# HS_MASTER_SHIELD_MAX485_V1.net
KiCad netlist of a schematic drawn in EAGLE
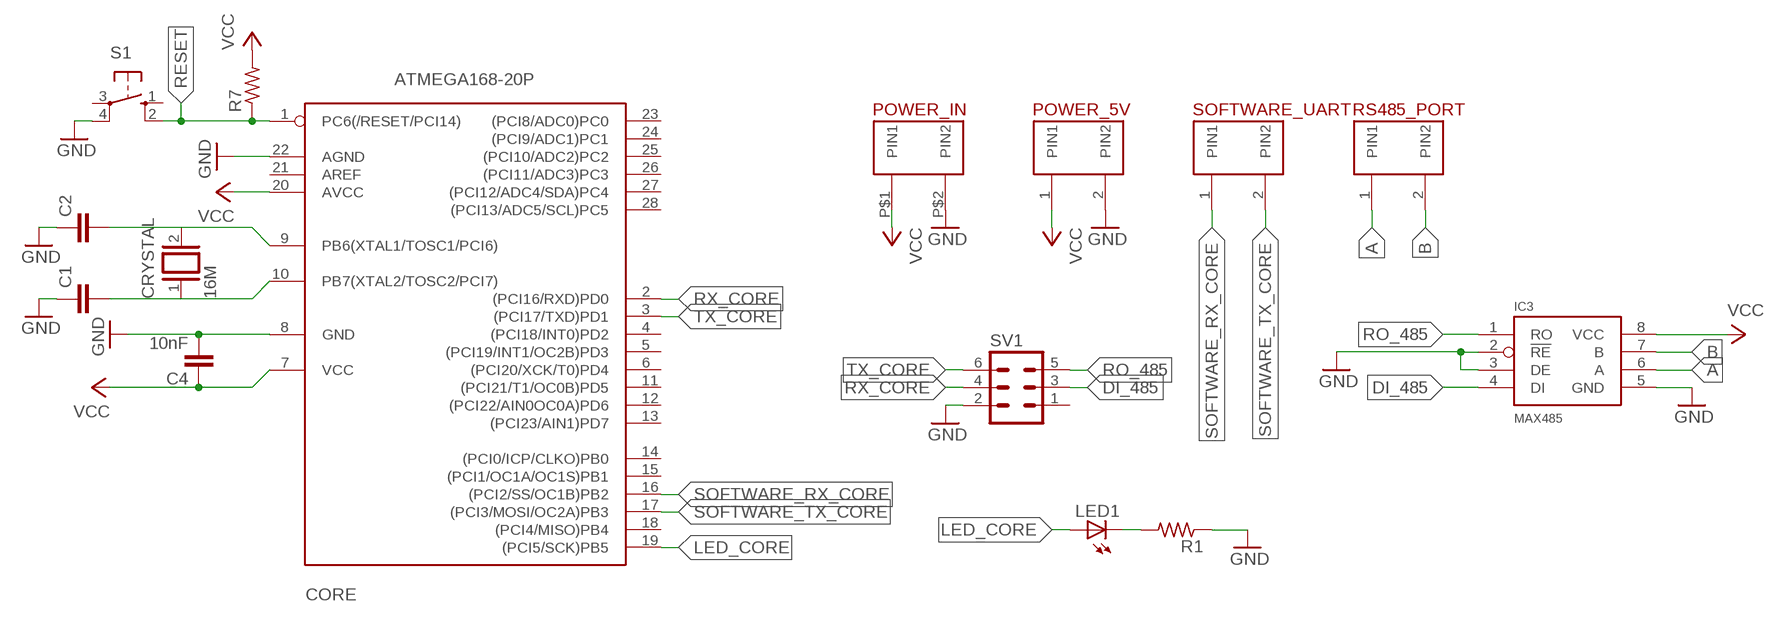
[diagram p0: schematic, sheet 1]

(export (version "E")
  (design (tool "Eeschema 10.0.6"))
  (components
    (comp (ref "C1")
      (value "C-EU025-024X044")
      (footprint "eagle-import:C025-024X044")
      (libsource (lib "eagle-import") (part "C-EU025-024X044"))
    )
    (comp (ref "C2")
      (value "C-EU025-024X044")
      (footprint "eagle-import:C025-024X044")
      (libsource (lib "eagle-import") (part "C-EU025-024X044"))
    )
    (comp (ref "C4")
      (value "10nF")
      (footprint "eagle-import:C5B2.5")
      (libsource (lib "eagle-import") (part "C5/2.5"))
    )
    (comp (ref "CORE")
      (value "ATMEGA168-20P")
      (footprint "eagle-import:DIL28-3")
      (libsource (lib "eagle-import") (part "ATMEGA168P-20"))
    )
    (comp (ref "CRYSTAL")
      (value "16M")
      (footprint "eagle-import:QS")
      (libsource (lib "eagle-import") (part "XTAL/S"))
    )
    (comp (ref "IC3")
      (value "MAX485")
      (footprint "eagle-import:DIP8")
      (libsource (lib "eagle-import") (part "MAX485"))
    )
    (comp (ref "LED1")
      (value "LED3MM")
      (footprint "eagle-import:LED3MM")
      (libsource (lib "eagle-import") (part "LED3MM"))
    )
    (comp (ref "POWER_5V")
      (value "7325")
      (footprint "eagle-import:2.54MM")
      (libsource (lib "eagle-import") (part "7325"))
    )
    (comp (ref "POWER_IN")
      (value "4396")
      (footprint "eagle-import:4MM")
      (libsource (lib "eagle-import") (part "4396"))
    )
    (comp (ref "R1")
      (value "R-US_0207/10")
      (footprint "eagle-import:0207_10")
      (libsource (lib "eagle-import") (part "R-US_0207/10"))
    )
    (comp (ref "R7")
      (value "R-US_0207/10")
      (footprint "eagle-import:0207_10")
      (libsource (lib "eagle-import") (part "R-US_0207/10"))
    )
    (comp (ref "RS485_PORT")
      (value "7325")
      (footprint "eagle-import:2.54MM")
      (libsource (lib "eagle-import") (part "7325"))
    )
    (comp (ref "S1")
      (value "10-XX")
      (footprint "eagle-import:B3F-10XX")
      (fields (field (name "MPN") "B3F-1000"))
      (libsource (lib "eagle-import") (part "10-XX"))
    )
    (comp (ref "SOFTWARE_UART")
      (value "7325")
      (footprint "eagle-import:2.54MM")
      (libsource (lib "eagle-import") (part "7325"))
    )
    (comp (ref "SV1")
      (value "MA03-2")
      (footprint "eagle-import:MA03-2")
      (libsource (lib "eagle-import") (part "MA03-2"))
    )
  )
  (nets
    (net (code "1") (name "A") (class "Default")
      (node (ref "IC3") (pin "6") (pinfunction "A_6") (pintype "bidirectional"))
      (node (ref "RS485_PORT") (pin "1") (pinfunction "PIN1_1") (pintype "bidirectional"))
    )
    (net (code "2") (name "B") (class "Default")
      (node (ref "IC3") (pin "7") (pinfunction "B_7") (pintype "bidirectional"))
      (node (ref "RS485_PORT") (pin "2") (pinfunction "PIN2_2") (pintype "bidirectional"))
    )
    (net (code "3") (name "DI_485") (class "Default")
      (node (ref "IC3") (pin "4") (pinfunction "DI_4") (pintype "bidirectional"))
      (node (ref "SV1") (pin "3") (pinfunction "3_3") (pintype "passive"))
    )
    (net (code "4") (name "GND") (class "Default")
      (node (ref "C1") (pin "1") (pinfunction "1_1") (pintype "passive"))
      (node (ref "C2") (pin "1") (pinfunction "1_1") (pintype "passive"))
      (node (ref "C4") (pin "2") (pinfunction "2_2") (pintype "passive"))
      (node (ref "CORE") (pin "22") (pinfunction "AGND_22") (pintype "bidirectional"))
      (node (ref "CORE") (pin "8") (pinfunction "GND_8") (pintype "bidirectional"))
      (node (ref "IC3") (pin "2") (pinfunction "~{RE}_2") (pintype "bidirectional"))
      (node (ref "IC3") (pin "3") (pinfunction "DE_3") (pintype "bidirectional"))
      (node (ref "IC3") (pin "5") (pinfunction "GND_5") (pintype "bidirectional"))
      (node (ref "POWER_5V") (pin "2") (pinfunction "PIN2_2") (pintype "bidirectional"))
      (node (ref "POWER_IN") (pin "P$2") (pinfunction "PIN2_P$2") (pintype "bidirectional"))
      (node (ref "R1") (pin "1") (pinfunction "1_1") (pintype "passive"))
      (node (ref "S1") (pin "4") (pinfunction "P1_4") (pintype "passive"))
      (node (ref "SV1") (pin "2") (pinfunction "2_2") (pintype "passive"))
    )
    (net (code "5") (name "LED_CORE") (class "Default")
      (node (ref "CORE") (pin "19") (pinfunction "(PCI5/SCK)PB5_19") (pintype "bidirectional"))
      (node (ref "LED1") (pin "A") (pinfunction "A_A") (pintype "passive"))
    )
    (net (code "6") (name "Net-(CORE-PB6(XTAL1{slash}TOSC1{slash}PCI6))") (class "Default")
      (node (ref "C2") (pin "2") (pinfunction "2_2") (pintype "passive"))
      (node (ref "CORE") (pin "9") (pinfunction "PB6(XTAL1/TOSC1/PCI6)_9") (pintype "bidirectional"))
      (node (ref "CRYSTAL") (pin "2") (pinfunction "2_2") (pintype "passive"))
    )
    (net (code "7") (name "Net-(CORE-PB7(XTAL2{slash}TOSC2{slash}PCI7))") (class "Default")
      (node (ref "C1") (pin "2") (pinfunction "2_2") (pintype "passive"))
      (node (ref "CORE") (pin "10") (pinfunction "PB7(XTAL2/TOSC2/PCI7)_10") (pintype "bidirectional"))
      (node (ref "CRYSTAL") (pin "1") (pinfunction "1_1") (pintype "passive"))
    )
    (net (code "8") (name "Net-(LED1-C)") (class "Default")
      (node (ref "LED1") (pin "K") (pinfunction "C_K") (pintype "passive"))
      (node (ref "R1") (pin "2") (pinfunction "2_2") (pintype "passive"))
    )
    (net (code "9") (name "RESET") (class "Default")
      (node (ref "CORE") (pin "1") (pinfunction "PC6(/RESET/PCI14)_1") (pintype "bidirectional"))
      (node (ref "R7") (pin "1") (pinfunction "1_1") (pintype "passive"))
      (node (ref "S1") (pin "2") (pinfunction "S1_2") (pintype "passive"))
    )
    (net (code "10") (name "RO_485") (class "Default")
      (node (ref "IC3") (pin "1") (pinfunction "RO_1") (pintype "bidirectional"))
      (node (ref "SV1") (pin "5") (pinfunction "5_5") (pintype "passive"))
    )
    (net (code "11") (name "RX_CORE") (class "Default")
      (node (ref "CORE") (pin "2") (pinfunction "(PCI16/RXD)PD0_2") (pintype "bidirectional"))
      (node (ref "SV1") (pin "4") (pinfunction "4_4") (pintype "passive"))
    )
    (net (code "12") (name "SOFTWARE_RX_CORE") (class "Default")
      (node (ref "CORE") (pin "16") (pinfunction "(PCI2/SS/OC1B)PB2_16") (pintype "bidirectional"))
      (node (ref "SOFTWARE_UART") (pin "1") (pinfunction "PIN1_1") (pintype "bidirectional"))
    )
    (net (code "13") (name "SOFTWARE_TX_CORE") (class "Default")
      (node (ref "CORE") (pin "17") (pinfunction "(PCI3/MOSI/OC2A)PB3_17") (pintype "bidirectional"))
      (node (ref "SOFTWARE_UART") (pin "2") (pinfunction "PIN2_2") (pintype "bidirectional"))
    )
    (net (code "14") (name "TX_CORE") (class "Default")
      (node (ref "CORE") (pin "3") (pinfunction "(PCI17/TXD)PD1_3") (pintype "bidirectional"))
      (node (ref "SV1") (pin "6") (pinfunction "6_6") (pintype "passive"))
    )
    (net (code "15") (name "VCC") (class "Default")
      (node (ref "C4") (pin "1") (pinfunction "1_1") (pintype "passive"))
      (node (ref "CORE") (pin "20") (pinfunction "AVCC_20") (pintype "bidirectional"))
      (node (ref "CORE") (pin "7") (pinfunction "VCC_7") (pintype "bidirectional"))
      (node (ref "IC3") (pin "8") (pinfunction "VCC_8") (pintype "bidirectional"))
      (node (ref "POWER_5V") (pin "1") (pinfunction "PIN1_1") (pintype "bidirectional"))
      (node (ref "POWER_IN") (pin "P$1") (pinfunction "PIN1_P$1") (pintype "bidirectional"))
      (node (ref "R7") (pin "2") (pinfunction "2_2") (pintype "passive"))
    )
    (net (code "16") (name "unconnected-(CORE-(PCI0{slash}ICP{slash}CLKO)PB0-Pad14)") (class "Default")
      (node (ref "CORE") (pin "14") (pinfunction "(PCI0/ICP/CLKO)PB0_14") (pintype "bidirectional"))
    )
    (net (code "17") (name "unconnected-(CORE-(PCI1{slash}OC1A{slash}OC1S)PB1-Pad15)") (class "Default")
      (node (ref "CORE") (pin "15") (pinfunction "(PCI1/OC1A/OC1S)PB1_15") (pintype "bidirectional"))
    )
    (net (code "18") (name "unconnected-(CORE-(PCI4{slash}MISO)PB4-Pad18)") (class "Default")
      (node (ref "CORE") (pin "18") (pinfunction "(PCI4/MISO)PB4_18") (pintype "bidirectional"))
    )
    (net (code "19") (name "unconnected-(CORE-(PCI8{slash}ADC0)PC0-Pad23)") (class "Default")
      (node (ref "CORE") (pin "23") (pinfunction "(PCI8/ADC0)PC0_23") (pintype "bidirectional"))
    )
    (net (code "20") (name "unconnected-(CORE-(PCI9{slash}ADC1)PC1-Pad24)") (class "Default")
      (node (ref "CORE") (pin "24") (pinfunction "(PCI9/ADC1)PC1_24") (pintype "bidirectional"))
    )
    (net (code "21") (name "unconnected-(CORE-(PCI10{slash}ADC2)PC2-Pad25)") (class "Default")
      (node (ref "CORE") (pin "25") (pinfunction "(PCI10/ADC2)PC2_25") (pintype "bidirectional"))
    )
    (net (code "22") (name "unconnected-(CORE-(PCI11{slash}ADC3)PC3-Pad26)") (class "Default")
      (node (ref "CORE") (pin "26") (pinfunction "(PCI11/ADC3)PC3_26") (pintype "bidirectional"))
    )
    (net (code "23") (name "unconnected-(CORE-(PCI12{slash}ADC4{slash}SDA)PC4-Pad27)") (class "Default")
      (node (ref "CORE") (pin "27") (pinfunction "(PCI12/ADC4/SDA)PC4_27") (pintype "bidirectional"))
    )
    (net (code "24") (name "unconnected-(CORE-(PCI13{slash}ADC5{slash}SCL)PC5-Pad28)") (class "Default")
      (node (ref "CORE") (pin "28") (pinfunction "(PCI13/ADC5/SCL)PC5_28") (pintype "bidirectional"))
    )
    (net (code "25") (name "unconnected-(CORE-(PCI18{slash}INT0)PD2-Pad4)") (class "Default")
      (node (ref "CORE") (pin "4") (pinfunction "(PCI18/INT0)PD2_4") (pintype "bidirectional"))
    )
    (net (code "26") (name "unconnected-(CORE-(PCI19{slash}INT1{slash}OC2B)PD3-Pad5)") (class "Default")
      (node (ref "CORE") (pin "5") (pinfunction "(PCI19/INT1/OC2B)PD3_5") (pintype "bidirectional"))
    )
    (net (code "27") (name "unconnected-(CORE-(PCI20{slash}XCK{slash}T0)PD4-Pad6)") (class "Default")
      (node (ref "CORE") (pin "6") (pinfunction "(PCI20/XCK/T0)PD4_6") (pintype "bidirectional"))
    )
    (net (code "28") (name "unconnected-(CORE-(PCI21{slash}T1{slash}OC0B)PD5-Pad11)") (class "Default")
      (node (ref "CORE") (pin "11") (pinfunction "(PCI21/T1/OC0B)PD5_11") (pintype "bidirectional"))
    )
    (net (code "29") (name "unconnected-(CORE-(PCI22{slash}AIN0OC0A)PD6-Pad12)") (class "Default")
      (node (ref "CORE") (pin "12") (pinfunction "(PCI22/AIN0OC0A)PD6_12") (pintype "bidirectional"))
    )
    (net (code "30") (name "unconnected-(CORE-(PCI23{slash}AIN1)PD7-Pad13)") (class "Default")
      (node (ref "CORE") (pin "13") (pinfunction "(PCI23/AIN1)PD7_13") (pintype "bidirectional"))
    )
    (net (code "31") (name "unconnected-(CORE-AREF-Pad21)") (class "Default")
      (node (ref "CORE") (pin "21") (pinfunction "AREF_21") (pintype "bidirectional"))
    )
    (net (code "32") (name "unconnected-(S1-P-Pad3)") (class "Default")
      (node (ref "S1") (pin "3") (pinfunction "P_3") (pintype "passive"))
    )
    (net (code "33") (name "unconnected-(S1-S-Pad1)") (class "Default")
      (node (ref "S1") (pin "1") (pinfunction "S_1") (pintype "passive"))
    )
    (net (code "34") (name "unconnected-(SV1-Pad1)") (class "Default")
      (node (ref "SV1") (pin "1") (pinfunction "1_1") (pintype "passive"))
    )
  )
)
